# Sheet1.net
KiCad netlist of a schematic drawn in Altium Designer
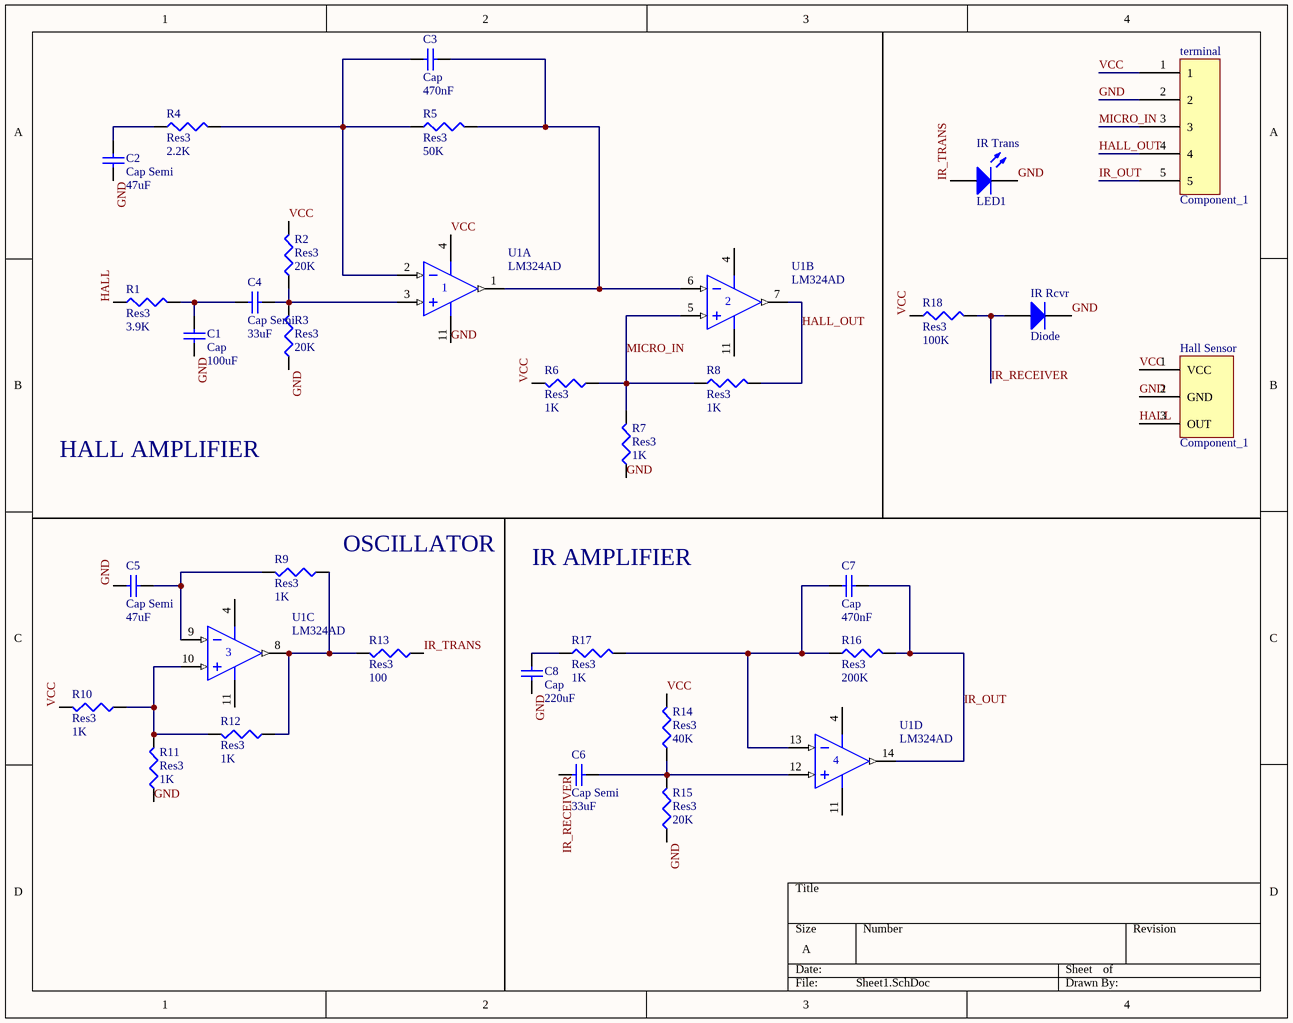
[diagram p0: Sheet1.SchDoc]

(export (version "E")
  (design (tool "Eeschema 10.0.6"))
  (components
    (comp (ref "C1")
      (value "Cap")
      (footprint "10TPB220M")
      (description "Capacitor")
      (fields (field (name "ALTIUM_VALUE") "100uF") (field (name "PUBLISHER") "Altium Limited"))
      (libsource (lib "Miscellaneous Devices") (part "Cap"))
    )
    (comp (ref "C2")
      (value "Cap Semi")
      (footprint "C1206")
      (description "Capacitor (Semiconductor SIM Model)")
      (fields (field (name "ALTIUM_VALUE") "47uF") (field (name "PUBLISHER") "Altium Limited"))
      (libsource (lib "Miscellaneous Devices") (part "Cap Semi"))
    )
    (comp (ref "C3")
      (value "Cap")
      (footprint "J1-0603")
      (description "Capacitor")
      (fields (field (name "ALTIUM_VALUE") "470nF") (field (name "PUBLISHER") "Altium Limited"))
      (libsource (lib "Miscellaneous Devices") (part "Cap"))
    )
    (comp (ref "C4")
      (value "Cap Semi")
      (footprint "C1210")
      (description "Capacitor (Semiconductor SIM Model)")
      (fields (field (name "ALTIUM_VALUE") "33uF") (field (name "PUBLISHER") "Altium Limited"))
      (libsource (lib "Miscellaneous Devices") (part "Cap Semi"))
    )
    (comp (ref "C5")
      (value "Cap Semi")
      (footprint "C1206")
      (description "Capacitor (Semiconductor SIM Model)")
      (fields (field (name "ALTIUM_VALUE") "47uF") (field (name "PUBLISHER") "Altium Limited"))
      (libsource (lib "Miscellaneous Devices") (part "Cap Semi"))
    )
    (comp (ref "C6")
      (value "Cap Semi")
      (footprint "C1210")
      (description "Capacitor (Semiconductor SIM Model)")
      (fields (field (name "ALTIUM_VALUE") "33uF") (field (name "PUBLISHER") "Altium Limited"))
      (libsource (lib "Miscellaneous Devices") (part "Cap Semi"))
    )
    (comp (ref "C7")
      (value "Cap")
      (footprint "J1-0603")
      (description "Capacitor")
      (fields (field (name "ALTIUM_VALUE") "470nF") (field (name "PUBLISHER") "Altium Limited"))
      (libsource (lib "Miscellaneous Devices") (part "Cap"))
    )
    (comp (ref "C8")
      (value "Cap")
      (footprint "10TPB220M")
      (description "Capacitor")
      (fields (field (name "ALTIUM_VALUE") "220uF") (field (name "PUBLISHER") "Altium Limited"))
      (libsource (lib "Miscellaneous Devices") (part "Cap"))
    )
    (comp (ref "Hall Sensor")
      (value "Component_1")
      (footprint "PCBComponent_1")
      (libsource (lib "hallSensor") (part "Component_1"))
    )
    (comp (ref "IR Rcvr")
      (value "Diode")
      (footprint "Miscellaneous Devices:PIN2")
      (description "Default Diode")
      (fields (field (name "PUBLISHER") "Altium Limited"))
      (libsource (lib "Miscellaneous Devices") (part "Diode"))
    )
    (comp (ref "IR Trans")
      (value "LED1")
      (footprint "PIN2")
      (description "Typical RED GaAs LED")
      (fields (field (name "PUBLISHER") "Altium Limited"))
      (libsource (lib "Miscellaneous Devices") (part "LED1"))
    )
    (comp (ref "R1")
      (value "Res3")
      (footprint "J1-0603")
      (description "Resistor")
      (fields (field (name "ALTIUM_VALUE") "3.9K") (field (name "PUBLISHER") "Altium Limited"))
      (libsource (lib "Miscellaneous Devices") (part "Res3"))
    )
    (comp (ref "R2")
      (value "Res3")
      (footprint "J1-0603")
      (description "Resistor")
      (fields (field (name "ALTIUM_VALUE") "20K") (field (name "PUBLISHER") "Altium Limited"))
      (libsource (lib "Miscellaneous Devices") (part "Res3"))
    )
    (comp (ref "R3")
      (value "Res3")
      (footprint "J1-0603")
      (description "Resistor")
      (fields (field (name "ALTIUM_VALUE") "20K") (field (name "PUBLISHER") "Altium Limited"))
      (libsource (lib "Miscellaneous Devices") (part "Res3"))
    )
    (comp (ref "R4")
      (value "Res3")
      (footprint "J1-0603")
      (description "Resistor")
      (fields (field (name "ALTIUM_VALUE") "2.2K") (field (name "PUBLISHER") "Altium Limited"))
      (libsource (lib "Miscellaneous Devices") (part "Res3"))
    )
    (comp (ref "R5")
      (value "Res3")
      (footprint "J1-0603")
      (description "Resistor")
      (fields (field (name "ALTIUM_VALUE") "50K") (field (name "PUBLISHER") "Altium Limited"))
      (libsource (lib "Miscellaneous Devices") (part "Res3"))
    )
    (comp (ref "R6")
      (value "Res3")
      (footprint "J1-0603")
      (description "Resistor")
      (fields (field (name "ALTIUM_VALUE") "1K") (field (name "PUBLISHER") "Altium Limited"))
      (libsource (lib "Miscellaneous Devices") (part "Res3"))
    )
    (comp (ref "R7")
      (value "Res3")
      (footprint "J1-0603")
      (description "Resistor")
      (fields (field (name "ALTIUM_VALUE") "1K") (field (name "PUBLISHER") "Altium Limited"))
      (libsource (lib "Miscellaneous Devices") (part "Res3"))
    )
    (comp (ref "R8")
      (value "Res3")
      (footprint "J1-0603")
      (description "Resistor")
      (fields (field (name "ALTIUM_VALUE") "1K") (field (name "PUBLISHER") "Altium Limited"))
      (libsource (lib "Miscellaneous Devices") (part "Res3"))
    )
    (comp (ref "R9")
      (value "Res3")
      (footprint "J1-0603")
      (description "Resistor")
      (fields (field (name "ALTIUM_VALUE") "1K") (field (name "PUBLISHER") "Altium Limited"))
      (libsource (lib "Miscellaneous Devices") (part "Res3"))
    )
    (comp (ref "R10")
      (value "Res3")
      (footprint "J1-0603")
      (description "Resistor")
      (fields (field (name "ALTIUM_VALUE") "1K") (field (name "PUBLISHER") "Altium Limited"))
      (libsource (lib "Miscellaneous Devices") (part "Res3"))
    )
    (comp (ref "R11")
      (value "Res3")
      (footprint "J1-0603")
      (description "Resistor")
      (fields (field (name "ALTIUM_VALUE") "1K") (field (name "PUBLISHER") "Altium Limited"))
      (libsource (lib "Miscellaneous Devices") (part "Res3"))
    )
    (comp (ref "R12")
      (value "Res3")
      (footprint "J1-0603")
      (description "Resistor")
      (fields (field (name "ALTIUM_VALUE") "1K") (field (name "PUBLISHER") "Altium Limited"))
      (libsource (lib "Miscellaneous Devices") (part "Res3"))
    )
    (comp (ref "R13")
      (value "Res3")
      (footprint "J1-0603")
      (description "Resistor")
      (fields (field (name "ALTIUM_VALUE") "100") (field (name "PUBLISHER") "Altium Limited"))
      (libsource (lib "Miscellaneous Devices") (part "Res3"))
    )
    (comp (ref "R14")
      (value "Res3")
      (footprint "J1-0603")
      (description "Resistor")
      (fields (field (name "ALTIUM_VALUE") "40K") (field (name "PUBLISHER") "Altium Limited"))
      (libsource (lib "Miscellaneous Devices") (part "Res3"))
    )
    (comp (ref "R15")
      (value "Res3")
      (footprint "J1-0603")
      (description "Resistor")
      (fields (field (name "ALTIUM_VALUE") "20K") (field (name "PUBLISHER") "Altium Limited"))
      (libsource (lib "Miscellaneous Devices") (part "Res3"))
    )
    (comp (ref "R16")
      (value "Res3")
      (footprint "J1-0603")
      (description "Resistor")
      (fields (field (name "ALTIUM_VALUE") "200K") (field (name "PUBLISHER") "Altium Limited"))
      (libsource (lib "Miscellaneous Devices") (part "Res3"))
    )
    (comp (ref "R17")
      (value "Res3")
      (footprint "J1-0603")
      (description "Resistor")
      (fields (field (name "ALTIUM_VALUE") "1K") (field (name "PUBLISHER") "Altium Limited"))
      (libsource (lib "Miscellaneous Devices") (part "Res3"))
    )
    (comp (ref "R18")
      (value "Res3")
      (footprint "J1-0603")
      (description "Resistor")
      (fields (field (name "ALTIUM_VALUE") "100K") (field (name "PUBLISHER") "Altium Limited"))
      (libsource (lib "Miscellaneous Devices") (part "Res3"))
    )
    (comp (ref "terminal")
      (value "Component_1")
      (footprint "PCBComponent_1")
      (libsource (lib "terminal") (part "Component_1"))
    )
    (comp (ref "U1")
      (value "LM324AD")
      (footprint "751A-03_N")
      (description "Quad Differential Input, Low-Power Operational Amplifier")
      (fields (field (name "PUBLISHER") "Altium Limited"))
      (libsource (lib "ON Semi Differential Amplifier") (part "LM324AD"))
    )
  )
  (nets
    (net (code "1") (name "/GND") (class "Default")
      (node (ref "C1") (pin "1") (pinfunction "1_1") (pintype "passive"))
      (node (ref "C2") (pin "1") (pinfunction "1_1") (pintype "passive"))
      (node (ref "C5") (pin "2") (pinfunction "2_2") (pintype "passive"))
      (node (ref "C8") (pin "1") (pinfunction "1_1") (pintype "passive"))
      (node (ref "Hall Sensor") (pin "2") (pinfunction "GND_2") (pintype "passive"))
      (node (ref "IR Rcvr") (pin "2") (pinfunction "K_2") (pintype "passive"))
      (node (ref "IR Trans") (pin "2") (pinfunction "K_2") (pintype "passive"))
      (node (ref "R11") (pin "1") (pinfunction "1_1") (pintype "passive"))
      (node (ref "R15") (pin "1") (pinfunction "1_1") (pintype "passive"))
      (node (ref "R3") (pin "1") (pinfunction "1_1") (pintype "passive"))
      (node (ref "R7") (pin "1") (pinfunction "1_1") (pintype "passive"))
      (node (ref "U1") (pin "11") (pinfunction "V-_11") (pintype "power_in"))
      (node (ref "terminal") (pin "2") (pinfunction "2_2") (pintype "passive"))
    )
    (net (code "2") (name "/HALL") (class "Default")
      (node (ref "Hall Sensor") (pin "3") (pinfunction "OUT_3") (pintype "passive"))
      (node (ref "R1") (pin "1") (pinfunction "1_1") (pintype "passive"))
    )
    (net (code "3") (name "/HALL_OUT") (class "Default")
      (node (ref "R8") (pin "2") (pinfunction "2_2") (pintype "passive"))
      (node (ref "U1") (pin "7") (pinfunction "OUT2_7") (pintype "output"))
      (node (ref "terminal") (pin "4") (pinfunction "4_4") (pintype "passive"))
    )
    (net (code "4") (name "/IR_OUT") (class "Default")
      (node (ref "C7") (pin "2") (pinfunction "2_2") (pintype "passive"))
      (node (ref "R16") (pin "2") (pinfunction "2_2") (pintype "passive"))
      (node (ref "U1") (pin "14") (pinfunction "OUT4_14") (pintype "output"))
      (node (ref "terminal") (pin "5") (pinfunction "5_5") (pintype "passive"))
    )
    (net (code "5") (name "/IR_RECEIVER") (class "Default")
      (node (ref "C6") (pin "1") (pinfunction "1_1") (pintype "passive"))
      (node (ref "IR Rcvr") (pin "1") (pinfunction "A_1") (pintype "passive"))
      (node (ref "R18") (pin "2") (pinfunction "2_2") (pintype "passive"))
    )
    (net (code "6") (name "/IR_TRANS") (class "Default")
      (node (ref "IR Trans") (pin "1") (pinfunction "A_1") (pintype "passive"))
      (node (ref "R13") (pin "1") (pinfunction "1_1") (pintype "passive"))
    )
    (net (code "7") (name "/MICRO_IN") (class "Default")
      (node (ref "R6") (pin "1") (pinfunction "1_1") (pintype "passive"))
      (node (ref "R7") (pin "2") (pinfunction "2_2") (pintype "passive"))
      (node (ref "R8") (pin "1") (pinfunction "1_1") (pintype "passive"))
      (node (ref "U1") (pin "5") (pinfunction "IN2+_5") (pintype "input"))
      (node (ref "terminal") (pin "3") (pinfunction "3_3") (pintype "passive"))
    )
    (net (code "8") (name "/VCC") (class "Default")
      (node (ref "Hall Sensor") (pin "1") (pinfunction "VCC_1") (pintype "passive"))
      (node (ref "R10") (pin "2") (pinfunction "2_2") (pintype "passive"))
      (node (ref "R14") (pin "2") (pinfunction "2_2") (pintype "passive"))
      (node (ref "R18") (pin "1") (pinfunction "1_1") (pintype "passive"))
      (node (ref "R2") (pin "2") (pinfunction "2_2") (pintype "passive"))
      (node (ref "R6") (pin "2") (pinfunction "2_2") (pintype "passive"))
      (node (ref "U1") (pin "4") (pinfunction "V+_4") (pintype "power_in"))
      (node (ref "terminal") (pin "1") (pinfunction "1_1") (pintype "passive"))
    )
    (net (code "9") (name "Net-(C1-Pad2)") (class "Default")
      (node (ref "C1") (pin "2") (pinfunction "2_2") (pintype "passive"))
      (node (ref "C4") (pin "1") (pinfunction "1_1") (pintype "passive"))
      (node (ref "R1") (pin "2") (pinfunction "2_2") (pintype "passive"))
    )
    (net (code "10") (name "Net-(C2-Pad2)") (class "Default")
      (node (ref "C2") (pin "2") (pinfunction "2_2") (pintype "passive"))
      (node (ref "R4") (pin "1") (pinfunction "1_1") (pintype "passive"))
    )
    (net (code "11") (name "Net-(C8-Pad2)") (class "Default")
      (node (ref "C8") (pin "2") (pinfunction "2_2") (pintype "passive"))
      (node (ref "R17") (pin "1") (pinfunction "1_1") (pintype "passive"))
    )
    (net (code "12") (name "Net-(U1A-IN1+)") (class "Default")
      (node (ref "C4") (pin "2") (pinfunction "2_2") (pintype "passive"))
      (node (ref "R2") (pin "1") (pinfunction "1_1") (pintype "passive"))
      (node (ref "R3") (pin "2") (pinfunction "2_2") (pintype "passive"))
      (node (ref "U1") (pin "3") (pinfunction "IN1+_3") (pintype "input"))
    )
    (net (code "13") (name "Net-(U1A-IN1-)") (class "Default")
      (node (ref "C3") (pin "1") (pinfunction "1_1") (pintype "passive"))
      (node (ref "R4") (pin "2") (pinfunction "2_2") (pintype "passive"))
      (node (ref "R5") (pin "1") (pinfunction "1_1") (pintype "passive"))
      (node (ref "U1") (pin "2") (pinfunction "IN1-_2") (pintype "input"))
    )
    (net (code "14") (name "Net-(U1A-OUT1)") (class "Default")
      (node (ref "C3") (pin "2") (pinfunction "2_2") (pintype "passive"))
      (node (ref "R5") (pin "2") (pinfunction "2_2") (pintype "passive"))
      (node (ref "U1") (pin "1") (pinfunction "OUT1_1") (pintype "output"))
      (node (ref "U1") (pin "6") (pinfunction "IN2-_6") (pintype "input"))
    )
    (net (code "15") (name "Net-(U1C-IN3+)") (class "Default")
      (node (ref "R10") (pin "1") (pinfunction "1_1") (pintype "passive"))
      (node (ref "R11") (pin "2") (pinfunction "2_2") (pintype "passive"))
      (node (ref "R12") (pin "2") (pinfunction "2_2") (pintype "passive"))
      (node (ref "U1") (pin "10") (pinfunction "IN3+_10") (pintype "input"))
    )
    (net (code "16") (name "Net-(U1C-IN3-)") (class "Default")
      (node (ref "C5") (pin "1") (pinfunction "1_1") (pintype "passive"))
      (node (ref "R9") (pin "2") (pinfunction "2_2") (pintype "passive"))
      (node (ref "U1") (pin "9") (pinfunction "IN3-_9") (pintype "input"))
    )
    (net (code "17") (name "Net-(U1C-OUT3)") (class "Default")
      (node (ref "R12") (pin "1") (pinfunction "1_1") (pintype "passive"))
      (node (ref "R13") (pin "2") (pinfunction "2_2") (pintype "passive"))
      (node (ref "R9") (pin "1") (pinfunction "1_1") (pintype "passive"))
      (node (ref "U1") (pin "8") (pinfunction "OUT3_8") (pintype "output"))
    )
    (net (code "18") (name "Net-(U1D-IN4+)") (class "Default")
      (node (ref "C6") (pin "2") (pinfunction "2_2") (pintype "passive"))
      (node (ref "R14") (pin "1") (pinfunction "1_1") (pintype "passive"))
      (node (ref "R15") (pin "2") (pinfunction "2_2") (pintype "passive"))
      (node (ref "U1") (pin "12") (pinfunction "IN4+_12") (pintype "input"))
    )
    (net (code "19") (name "Net-(U1D-IN4-)") (class "Default")
      (node (ref "C7") (pin "1") (pinfunction "1_1") (pintype "passive"))
      (node (ref "R16") (pin "1") (pinfunction "1_1") (pintype "passive"))
      (node (ref "R17") (pin "2") (pinfunction "2_2") (pintype "passive"))
      (node (ref "U1") (pin "13") (pinfunction "IN4-_13") (pintype "input"))
    )
    (net (code "20") (name "unconnected-(U1B-V+-Pad4)") (class "Default")
      (node (ref "U1") (pin "4") (pinfunction "V+_4") (pintype "power_in"))
    )
    (net (code "21") (name "unconnected-(U1B-V--Pad11)") (class "Default")
      (node (ref "U1") (pin "11") (pinfunction "V-_11") (pintype "power_in"))
    )
    (net (code "22") (name "unconnected-(U1C-V+-Pad4)") (class "Default")
      (node (ref "U1") (pin "4") (pinfunction "V+_4") (pintype "power_in"))
    )
    (net (code "23") (name "unconnected-(U1C-V--Pad11)") (class "Default")
      (node (ref "U1") (pin "11") (pinfunction "V-_11") (pintype "power_in"))
    )
    (net (code "24") (name "unconnected-(U1D-V+-Pad4)") (class "Default")
      (node (ref "U1") (pin "4") (pinfunction "V+_4") (pintype "power_in"))
    )
    (net (code "25") (name "unconnected-(U1D-V--Pad11)") (class "Default")
      (node (ref "U1") (pin "11") (pinfunction "V-_11") (pintype "power_in"))
    )
  )
)
